# 1-Schematic_CarFan_controller_v2_1.net
KiCad netlist of a schematic drawn in EasyEDA
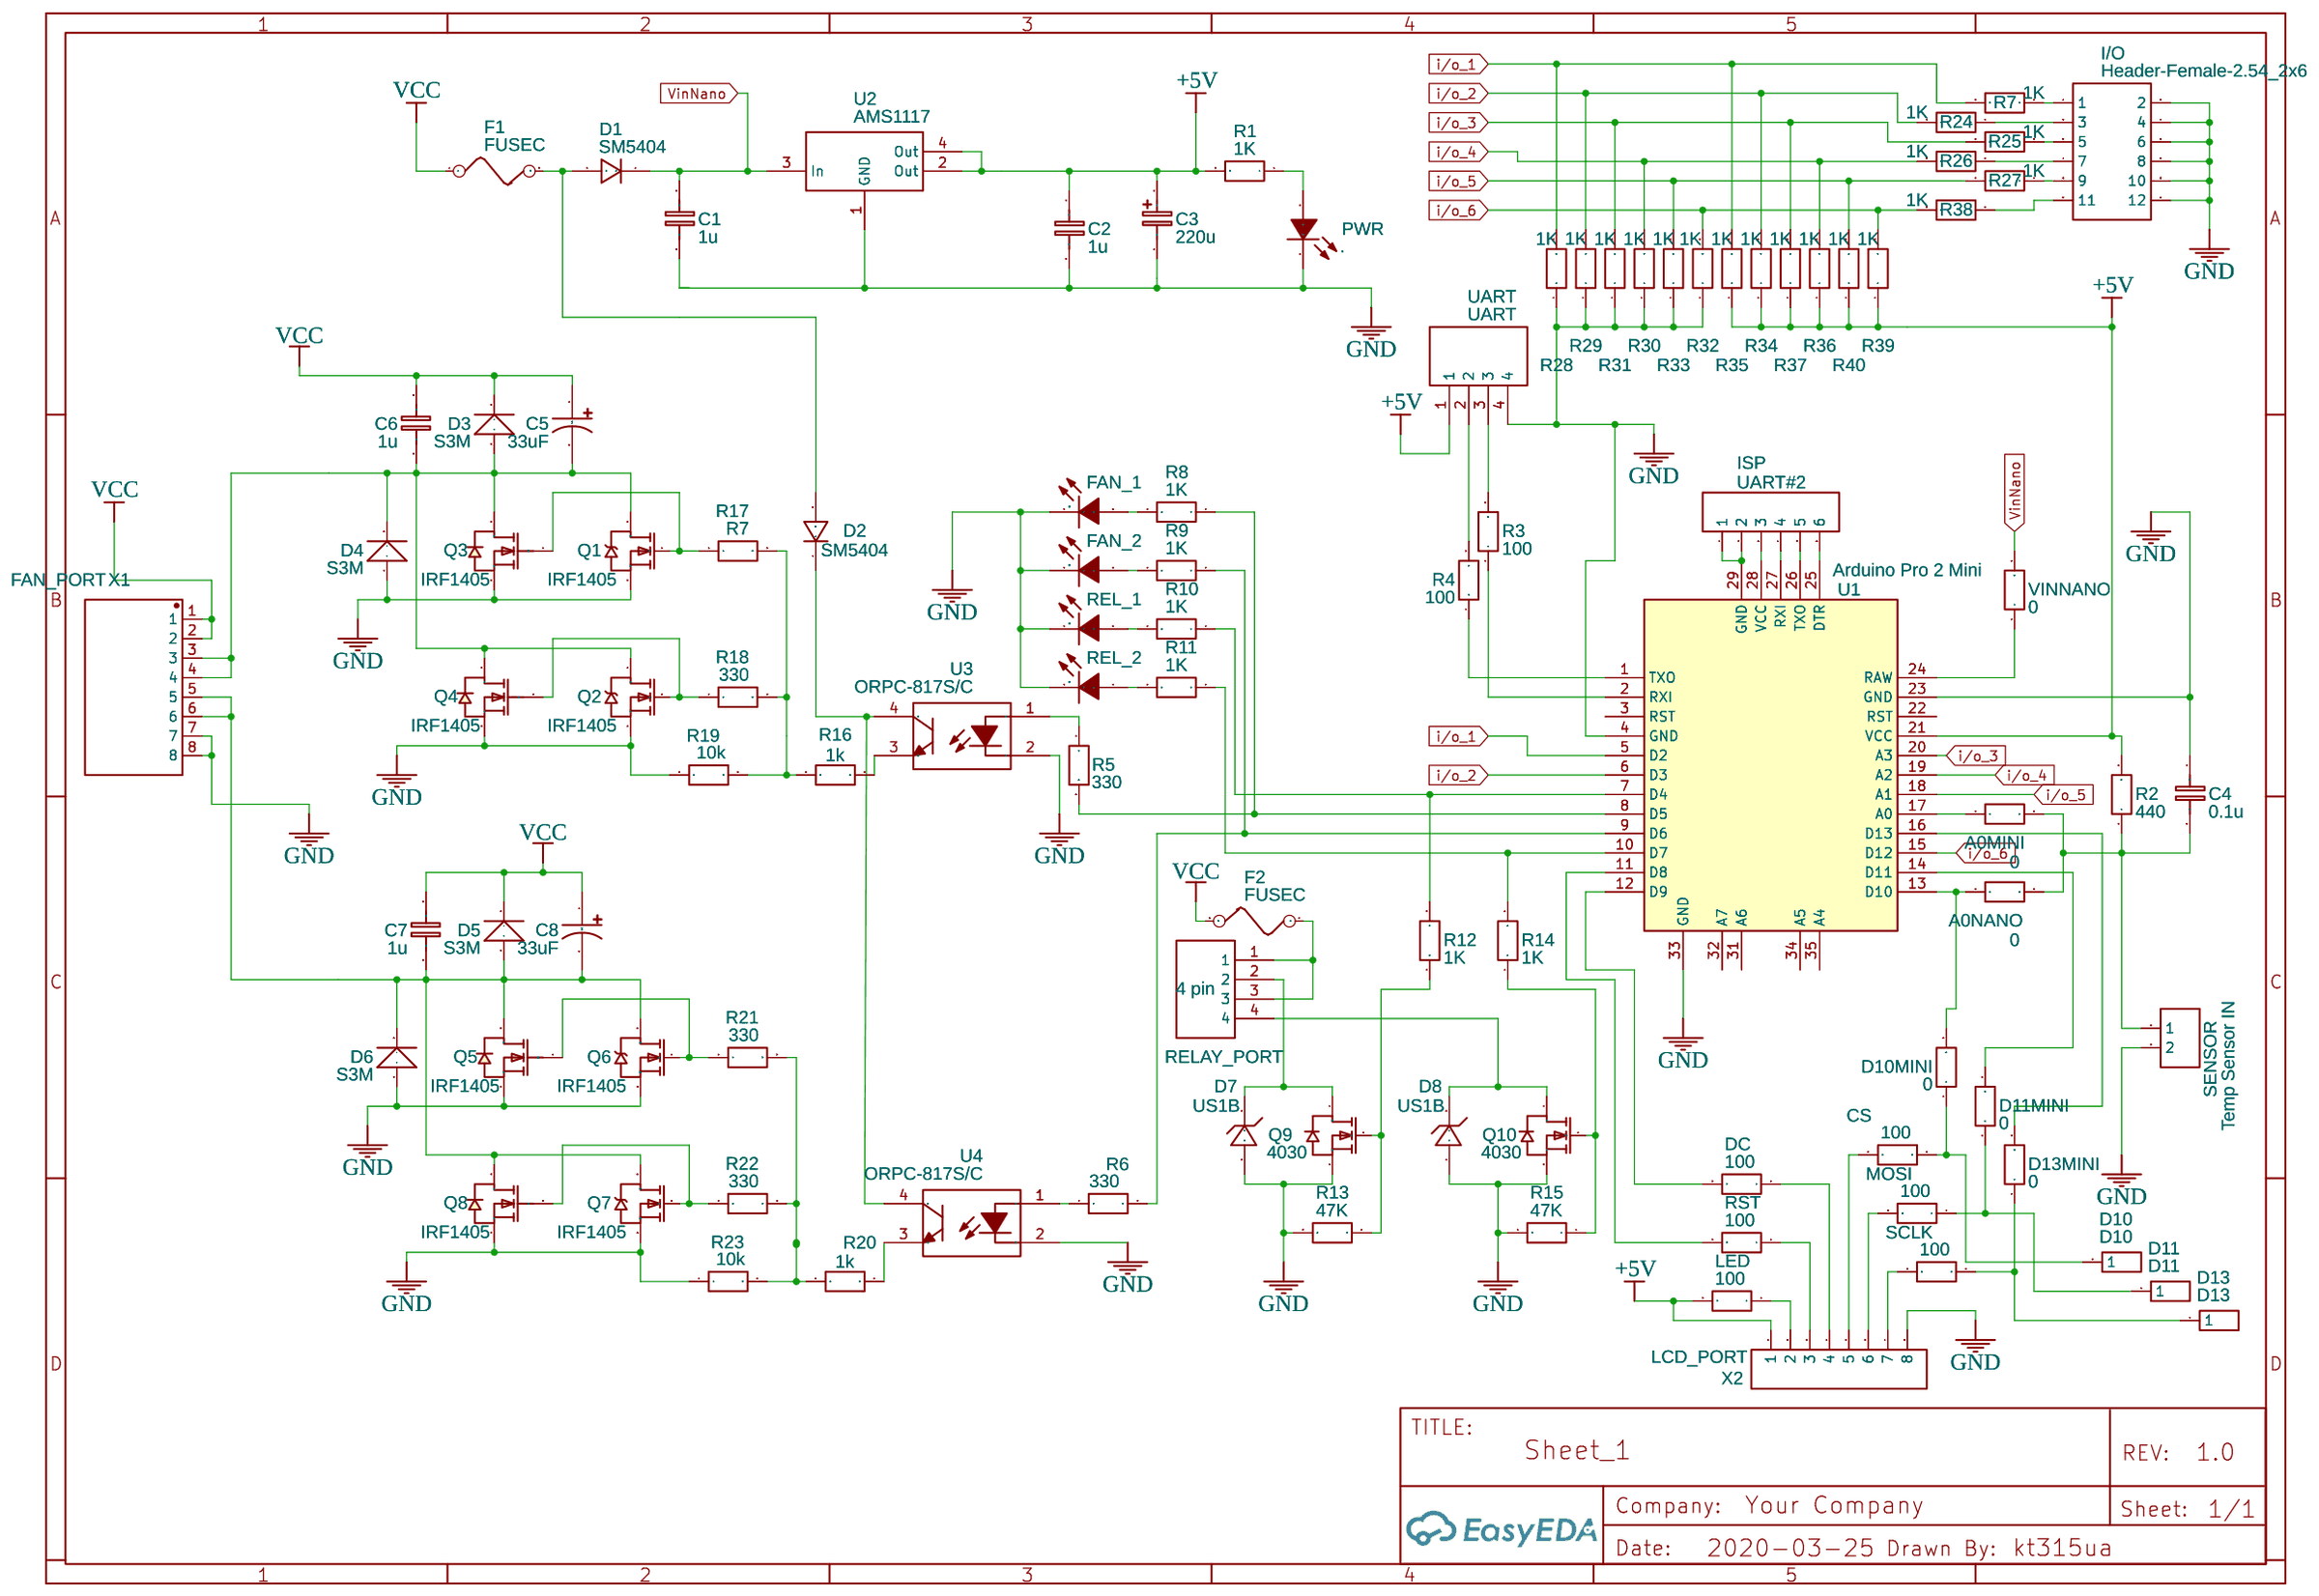
[diagram p0: schematic sheet]

(export (version "E")
  (design (tool "Eeschema 10.0.6"))
  (components
    (comp (ref "A0MINI") (value "0") (libsource (lib "") (part "Res_1206(1/4W)_EU_7")))
    (comp (ref "A0NANO") (value "0") (libsource (lib "") (part "Res_1206(1/4W)_EU_3")))
    (comp (ref "C1") (value "1u") (libsource (lib "") (part "Cap_1206_EU_4")))
    (comp (ref "C2") (value "1u") (libsource (lib "") (part "Cap_1206_EU_2")))
    (comp (ref "C3") (value "220u") (libsource (lib "") (part "Cap_Electrolytic(SMD)_D6.3XH5.5_EU")))
    (comp (ref "C4") (value "0.1u") (libsource (lib "") (part "Cap_1206_EU_3")))
    (comp (ref "C5")
      (value "33uF")
      (fields
        (field (name "BOM_Manufacturer Part") "EEEFK2A330P")
        (field (name "BOM_Supplier Part") "C178571")
      )
      (libsource (lib "") (part "EEEFK2A330P"))
    )
    (comp (ref "C6") (value "1u") (libsource (lib "") (part "Cap_1206_EU")))
    (comp (ref "C7") (value "1u") (libsource (lib "") (part "Cap_1206_EU_1")))
    (comp (ref "C8")
      (value "33uF")
      (fields
        (field (name "BOM_Manufacturer Part") "EEEFK2A330P")
        (field (name "BOM_Supplier Part") "C178571")
      )
      (libsource (lib "") (part "EEEFK2A330P"))
    )
    (comp (ref "CS") (value "100") (libsource (lib "") (part "Res_1206(1/4W)_EU_15")))
    (comp (ref "D1")
      (value "SM5404")
      (fields (field (name "BOM_Supplier Part") "C212808"))
      (libsource (lib "") (part "SM5404_1"))
    )
    (comp (ref "D2")
      (value "SM5404")
      (fields (field (name "BOM_Supplier Part") "C212808"))
      (libsource (lib "") (part "SM5404"))
    )
    (comp (ref "D3") (value "S3M") (libsource (lib "") (part "DDO-214AB")))
    (comp (ref "D4") (value "S3M") (libsource (lib "") (part "DDO-214AB")))
    (comp (ref "D5") (value "S3M") (libsource (lib "") (part "DDO-214AB")))
    (comp (ref "D6") (value "S3M") (libsource (lib "") (part "DDO-214AB")))
    (comp (ref "D7")
      (value "US1B")
      (fields
        (field (name "BOM_Manufacturer Part") "SMAZ12-13-F")
        (field (name "BOM_Supplier Part") "C110523")
      )
      (libsource (lib "") (part "SMAZ12-13-F(SMA(DO-214AC))"))
    )
    (comp (ref "D8")
      (value "US1B")
      (fields
        (field (name "BOM_Manufacturer Part") "SMAZ12-13-F")
        (field (name "BOM_Supplier Part") "C110523")
      )
      (libsource (lib "") (part "SMAZ12-13-F(SMA(DO-214AC))"))
    )
    (comp (ref "D10")
      (value "D10")
      (fields
        (field (name "BOM_Manufacturer Part") "Header-Male-2.54_1x1")
        (field (name "BOM_Supplier Part") "C81276")
      )
      (libsource (lib "") (part "Header-Male-2.54_1x1"))
    )
    (comp (ref "D10MINI") (value "0") (libsource (lib "") (part "Res_1206(1/4W)_EU_11")))
    (comp (ref "D11")
      (value "D11")
      (fields
        (field (name "BOM_Manufacturer Part") "Header-Male-2.54_1x1")
        (field (name "BOM_Supplier Part") "C81276")
      )
      (libsource (lib "") (part "Header-Male-2.54_1x1"))
    )
    (comp (ref "D11MINI") (value "0") (libsource (lib "") (part "Res_1206(1/4W)_EU_6")))
    (comp (ref "D13")
      (value "D13")
      (fields
        (field (name "BOM_Manufacturer Part") "Header-Male-2.54_1x1")
        (field (name "BOM_Supplier Part") "C81276")
      )
      (libsource (lib "") (part "Header-Male-2.54_1x1"))
    )
    (comp (ref "D13MINI") (value "0") (libsource (lib "") (part "Res_1206(1/4W)_EU_10")))
    (comp (ref "DC") (value "100") (libsource (lib "") (part "Res_1206(1/4W)_EU_14")))
    (comp (ref "F1") (value "FUSEC") (libsource (lib "") (part "FUSEC_1")))
    (comp (ref "F2") (value "FUSEC") (libsource (lib "") (part "FUSEC")))
    (comp (ref "FAN_1")
      (value ".")
      (fields
        (field (name "BOM_Manufacturer Part") "KT-1206Red LED")
        (field (name "BOM_Supplier Part") "C49018")
      )
      (libsource (lib "") (part "KT-1206Red LED"))
    )
    (comp (ref "FAN_2")
      (value ".")
      (fields
        (field (name "BOM_Manufacturer Part") "KT-1206Red LED")
        (field (name "BOM_Supplier Part") "C49018")
      )
      (libsource (lib "") (part "KT-1206Red LED"))
    )
    (comp (ref "FAN_PORT")
      (value "X1")
      (fields
        (field (name "BOM_Manufacturer Part") "Connector KF2510-8A")
        (field (name "BOM_Supplier Part") "C27837")
      )
      (libsource (lib "") (part "Connector_KF2510-8A-Fix"))
    )
    (comp (ref "I/O")
      (value "Header-Female-2.54_2x6")
      (fields (field (name "BOM_Supplier Part") "C36191"))
      (libsource (lib "") (part "Header-Female-2.54_2x6"))
    )
    (comp (ref "ISP")
      (value "UART#2")
      (fields
        (field (name "BOM_Manufacturer Part") "Female header 1*6p")
        (field (name "BOM_Supplier Part") "C40877")
      )
      (libsource (lib "") (part "Header-Female-2.54_1x6"))
    )
    (comp (ref "LCD_PORT")
      (value "X2")
      (fields
        (field (name "BOM_Manufacturer Part") "Female headerHDR1X8-2.54")
        (field (name "BOM_Supplier Part") "C27438")
      )
      (libsource (lib "") (part "Header-Female-2.54_1x8"))
    )
    (comp (ref "LED") (value "100") (libsource (lib "") (part "Res_1206(1/4W)_EU_13")))
    (comp (ref "MOSI") (value "100") (libsource (lib "") (part "Res_1206(1/4W)_EU_4")))
    (comp (ref "PWR")
      (value ".")
      (fields
        (field (name "BOM_Manufacturer Part") "KT-1206Red LED")
        (field (name "BOM_Supplier Part") "C49018")
      )
      (libsource (lib "") (part "KT-1206Red LED_2"))
    )
    (comp (ref "Q1")
      (value "IRF1405")
      (fields
        (field (name "BOM_Manufacturer Part") "IRF1405ZSTRLPBF")
        (field (name "BOM_Supplier Part") "C459941")
      )
      (libsource (lib "") (part "IRF1405ZSTRLPBF"))
    )
    (comp (ref "Q2")
      (value "IRF1405")
      (fields
        (field (name "BOM_Manufacturer Part") "IRF1405ZSTRLPBF")
        (field (name "BOM_Supplier Part") "C459941")
      )
      (libsource (lib "") (part "IRF1405ZSTRLPBF"))
    )
    (comp (ref "Q3")
      (value "IRF1405")
      (fields (field (name "BOM_Manufacturer Part") "IRF1405PBF") (field (name "BOM_Supplier Part") "C2559"))
      (libsource (lib "") (part "IRF1405PBF"))
    )
    (comp (ref "Q4")
      (value "IRF1405")
      (fields (field (name "BOM_Manufacturer Part") "IRF1405PBF") (field (name "BOM_Supplier Part") "C2559"))
      (libsource (lib "") (part "IRF1405PBF"))
    )
    (comp (ref "Q5")
      (value "IRF1405")
      (fields (field (name "BOM_Manufacturer Part") "IRF1405PBF") (field (name "BOM_Supplier Part") "C2559"))
      (libsource (lib "") (part "IRF1405PBF"))
    )
    (comp (ref "Q6")
      (value "IRF1405")
      (fields
        (field (name "BOM_Manufacturer Part") "IRF1405ZSTRLPBF")
        (field (name "BOM_Supplier Part") "C459941")
      )
      (libsource (lib "") (part "IRF1405ZSTRLPBF"))
    )
    (comp (ref "Q7")
      (value "IRF1405")
      (fields
        (field (name "BOM_Manufacturer Part") "IRF1405ZSTRLPBF")
        (field (name "BOM_Supplier Part") "C459941")
      )
      (libsource (lib "") (part "IRF1405ZSTRLPBF"))
    )
    (comp (ref "Q8")
      (value "IRF1405")
      (fields (field (name "BOM_Manufacturer Part") "IRF1405PBF") (field (name "BOM_Supplier Part") "C2559"))
      (libsource (lib "") (part "IRF1405PBF"))
    )
    (comp (ref "Q9")
      (value "4030")
      (fields
        (field (name "BOM_Manufacturer Part") "STD8N60DM2")
        (field (name "BOM_Supplier Part") "C457504")
      )
      (libsource (lib "") (part "STD8N60DM2"))
    )
    (comp (ref "Q10")
      (value "4030")
      (fields
        (field (name "BOM_Manufacturer Part") "STD8N60DM2")
        (field (name "BOM_Supplier Part") "C457504")
      )
      (libsource (lib "") (part "STD8N60DM2"))
    )
    (comp (ref "R1") (value "1K") (libsource (lib "") (part "Res_1206(1/4W)_EU_5")))
    (comp (ref "R2") (value "440") (libsource (lib "") (part "Res_1206(1/4W)_EU_1")))
    (comp (ref "R3") (value "100") (libsource (lib "") (part "Res_1206(1/4W)_EU_1")))
    (comp (ref "R4") (value "100") (libsource (lib "") (part "Res_1206(1/4W)_EU_1")))
    (comp (ref "R5") (value "330") (libsource (lib "") (part "Res_1206(1/4W)_EU_8")))
    (comp (ref "R6") (value "330") (libsource (lib "") (part "Res_1206(1/4W)_EU")))
    (comp (ref "R7") (value "1K") (libsource (lib "") (part "Res_1206(1/4W)_EU_5")))
    (comp (ref "R8") (value "1K") (libsource (lib "") (part "Res_1206(1/4W)_EU_5")))
    (comp (ref "R9") (value "1K") (libsource (lib "") (part "Res_1206(1/4W)_EU_5")))
    (comp (ref "R10") (value "1K") (libsource (lib "") (part "Res_1206(1/4W)_EU_5")))
    (comp (ref "R11") (value "1K") (libsource (lib "") (part "Res_1206(1/4W)_EU_5")))
    (comp (ref "R12") (value "1K") (libsource (lib "") (part "Res_1206(1/4W)_EU_1")))
    (comp (ref "R13") (value "47K") (libsource (lib "") (part "Res_1206(1/4W)_EU_5")))
    (comp (ref "R14") (value "1K") (libsource (lib "") (part "Res_1206(1/4W)_EU_1")))
    (comp (ref "R15") (value "47K") (libsource (lib "") (part "Res_1206(1/4W)_EU_5")))
    (comp (ref "R16") (value "1k") (libsource (lib "") (part "Res_1206(1/4W)_EU_5")))
    (comp (ref "R17") (value "R7") (libsource (lib "") (part "Res_1206(1/4W)_EU")))
    (comp (ref "R18") (value "330") (libsource (lib "") (part "Res_1206(1/4W)_EU")))
    (comp (ref "R19") (value "10k") (libsource (lib "") (part "Res_1206(1/4W)_EU")))
    (comp (ref "R20") (value "1k") (libsource (lib "") (part "Res_1206(1/4W)_EU_5")))
    (comp (ref "R21") (value "330") (libsource (lib "") (part "Res_1206(1/4W)_EU")))
    (comp (ref "R22") (value "330") (libsource (lib "") (part "Res_1206(1/4W)_EU")))
    (comp (ref "R23") (value "10k") (libsource (lib "") (part "Res_1206(1/4W)_EU")))
    (comp (ref "R24") (value "1K") (libsource (lib "") (part "Res_1206(1/4W)_EU_5")))
    (comp (ref "R25") (value "1K") (libsource (lib "") (part "Res_1206(1/4W)_EU_5")))
    (comp (ref "R26") (value "1K") (libsource (lib "") (part "Res_1206(1/4W)_EU_5")))
    (comp (ref "R27") (value "1K") (libsource (lib "") (part "Res_1206(1/4W)_EU_5")))
    (comp (ref "R28") (value "1K") (libsource (lib "") (part "Res_1206(1/4W)_EU_1")))
    (comp (ref "R29") (value "1K") (libsource (lib "") (part "Res_1206(1/4W)_EU_1")))
    (comp (ref "R30") (value "1K") (libsource (lib "") (part "Res_1206(1/4W)_EU_1")))
    (comp (ref "R31") (value "1K") (libsource (lib "") (part "Res_1206(1/4W)_EU_1")))
    (comp (ref "R32") (value "1K") (libsource (lib "") (part "Res_1206(1/4W)_EU_1")))
    (comp (ref "R33") (value "1K") (libsource (lib "") (part "Res_1206(1/4W)_EU_1")))
    (comp (ref "R34") (value "1K") (libsource (lib "") (part "Res_1206(1/4W)_EU_1")))
    (comp (ref "R35") (value "1K") (libsource (lib "") (part "Res_1206(1/4W)_EU_1")))
    (comp (ref "R36") (value "1K") (libsource (lib "") (part "Res_1206(1/4W)_EU_1")))
    (comp (ref "R37") (value "1K") (libsource (lib "") (part "Res_1206(1/4W)_EU_1")))
    (comp (ref "R38") (value "1K") (libsource (lib "") (part "Res_1206(1/4W)_EU_5")))
    (comp (ref "R39") (value "1K") (libsource (lib "") (part "Res_1206(1/4W)_EU_1")))
    (comp (ref "R40") (value "1K") (libsource (lib "") (part "Res_1206(1/4W)_EU_1")))
    (comp (ref "RELAY_PORT")
      (value "4 pin")
      (fields
        (field (name "BOM_Manufacturer Part") "220S-1*4P H=8.5MM Ytype Gold-plated")
        (field (name "BOM_Supplier Part") "C124413")
      )
      (libsource (lib "") (part "220S-1*4P H=8.5MM Ytype Gold-plated"))
    )
    (comp (ref "REL_1")
      (value ".")
      (fields
        (field (name "BOM_Manufacturer Part") "KT-1206Red LED")
        (field (name "BOM_Supplier Part") "C49018")
      )
      (libsource (lib "") (part "KT-1206Red LED_1"))
    )
    (comp (ref "REL_2")
      (value ".")
      (fields
        (field (name "BOM_Manufacturer Part") "KT-1206Red LED")
        (field (name "BOM_Supplier Part") "C49018")
      )
      (libsource (lib "") (part "KT-1206Red LED_1"))
    )
    (comp (ref "RST") (value "100") (libsource (lib "") (part "Res_1206(1/4W)_EU_2")))
    (comp (ref "SCLK") (value "100") (libsource (lib "") (part "Res_1206(1/4W)_EU_12")))
    (comp (ref "SENSOR")
      (value "Temp Sensor IN")
      (fields
        (field (name "BOM_Manufacturer Part") "2.54-1*2PFemale")
        (field (name "BOM_Supplier Part") "C49661")
      )
      (libsource (lib "") (part "Header-Female-2.54_1x2"))
    )
    (comp (ref "U1") (value "Arduino Pro 2 Mini") (libsource (lib "") (part "Arduino Pro 2 Mini_328_-_3.3V")))
    (comp (ref "U2")
      (value "AMS1117")
      (fields (field (name "BOM_Supplier Part") "C6186"))
      (libsource (lib "") (part "AMS1117"))
    )
    (comp (ref "U3")
      (value "ORPC-817S/C")
      (fields (field (name "BOM_Supplier Part") "C231230"))
      (libsource (lib "") (part "ORPC-817S/C"))
    )
    (comp (ref "U4")
      (value "ORPC-817S/C")
      (fields (field (name "BOM_Supplier Part") "C231230"))
      (libsource (lib "") (part "ORPC-817S/C"))
    )
    (comp (ref "UART")
      (value "UART")
      (fields
        (field (name "BOM_Manufacturer Part") "220S-1*4P H=8.5MM Ytype Gold-plated")
        (field (name "BOM_Supplier Part") "C124413")
      )
      (libsource (lib "") (part "220S-1*4P H=8.5MM Ytype Gold-plated_1"))
    )
    (comp (ref "VINNANO") (value "0") (libsource (lib "") (part "Res_1206(1/4W)_EU_9")))
  )
  (nets
    (net (code "1") (name "+5V") (class "Default")
      (node (ref "C2") (pin "1") (pinfunction "1_1") (pintype "unspecified"))
      (node (ref "C3") (pin "1") (pinfunction "1_1") (pintype "unspecified"))
      (node (ref "LCD_PORT") (pin "1") (pinfunction "1_1") (pintype "input"))
      (node (ref "LED") (pin "2") (pinfunction "2_2") (pintype "unspecified"))
      (node (ref "R1") (pin "2") (pinfunction "2_2") (pintype "unspecified"))
      (node (ref "R2") (pin "2") (pinfunction "2_2") (pintype "unspecified"))
      (node (ref "R34") (pin "1") (pinfunction "1_1") (pintype "unspecified"))
      (node (ref "R35") (pin "1") (pinfunction "1_1") (pintype "unspecified"))
      (node (ref "R36") (pin "1") (pinfunction "1_1") (pintype "unspecified"))
      (node (ref "R37") (pin "1") (pinfunction "1_1") (pintype "unspecified"))
      (node (ref "R39") (pin "1") (pinfunction "1_1") (pintype "unspecified"))
      (node (ref "R40") (pin "1") (pinfunction "1_1") (pintype "unspecified"))
      (node (ref "U1") (pin "21") (pinfunction "VCC_21") (pintype "unspecified"))
      (node (ref "U2") (pin "2") (pinfunction "Out_2") (pintype "unspecified"))
      (node (ref "U2") (pin "4") (pinfunction "Out_4") (pintype "unspecified"))
      (node (ref "UART") (pin "1") (pinfunction "1_1") (pintype "unspecified"))
    )
    (net (code "2") (name "GND") (class "Default")
      (node (ref "C1") (pin "2") (pinfunction "2_2") (pintype "unspecified"))
      (node (ref "C2") (pin "2") (pinfunction "2_2") (pintype "unspecified"))
      (node (ref "C3") (pin "2") (pinfunction "2_2") (pintype "unspecified"))
      (node (ref "C4") (pin "1") (pinfunction "1_1") (pintype "unspecified"))
      (node (ref "D4") (pin "1") (pinfunction "+_1") (pintype "unspecified"))
      (node (ref "D6") (pin "1") (pinfunction "+_1") (pintype "unspecified"))
      (node (ref "D7") (pin "1") (pinfunction "A_1") (pintype "unspecified"))
      (node (ref "D8") (pin "1") (pinfunction "A_1") (pintype "unspecified"))
      (node (ref "FAN_1") (pin "2") (pinfunction "K_2") (pintype "unspecified"))
      (node (ref "FAN_2") (pin "2") (pinfunction "K_2") (pintype "unspecified"))
      (node (ref "FAN_PORT") (pin "7") (pinfunction "7_7") (pintype "unspecified"))
      (node (ref "FAN_PORT") (pin "8") (pinfunction "8_8") (pintype "unspecified"))
      (node (ref "I/O") (pin "10") (pinfunction "10_10") (pintype "input"))
      (node (ref "I/O") (pin "12") (pinfunction "12_12") (pintype "input"))
      (node (ref "I/O") (pin "2") (pinfunction "2_2") (pintype "input"))
      (node (ref "I/O") (pin "4") (pinfunction "4_4") (pintype "input"))
      (node (ref "I/O") (pin "6") (pinfunction "6_6") (pintype "input"))
      (node (ref "I/O") (pin "8") (pinfunction "8_8") (pintype "input"))
      (node (ref "LCD_PORT") (pin "8") (pinfunction "8_8") (pintype "input"))
      (node (ref "PWR") (pin "2") (pinfunction "K_2") (pintype "unspecified"))
      (node (ref "Q1") (pin "3") (pinfunction "S_3") (pintype "unspecified"))
      (node (ref "Q10") (pin "3") (pinfunction "S_3") (pintype "unspecified"))
      (node (ref "Q2") (pin "3") (pinfunction "S_3") (pintype "unspecified"))
      (node (ref "Q3") (pin "3") (pinfunction "S_3") (pintype "unspecified"))
      (node (ref "Q4") (pin "3") (pinfunction "S_3") (pintype "unspecified"))
      (node (ref "Q5") (pin "3") (pinfunction "S_3") (pintype "unspecified"))
      (node (ref "Q6") (pin "3") (pinfunction "S_3") (pintype "unspecified"))
      (node (ref "Q7") (pin "3") (pinfunction "S_3") (pintype "unspecified"))
      (node (ref "Q8") (pin "3") (pinfunction "S_3") (pintype "unspecified"))
      (node (ref "Q9") (pin "3") (pinfunction "S_3") (pintype "unspecified"))
      (node (ref "R13") (pin "2") (pinfunction "2_2") (pintype "unspecified"))
      (node (ref "R15") (pin "2") (pinfunction "2_2") (pintype "unspecified"))
      (node (ref "R19") (pin "1") (pinfunction "1_1") (pintype "unspecified"))
      (node (ref "R23") (pin "1") (pinfunction "1_1") (pintype "unspecified"))
      (node (ref "R28") (pin "1") (pinfunction "1_1") (pintype "unspecified"))
      (node (ref "R29") (pin "1") (pinfunction "1_1") (pintype "unspecified"))
      (node (ref "R30") (pin "1") (pinfunction "1_1") (pintype "unspecified"))
      (node (ref "R31") (pin "1") (pinfunction "1_1") (pintype "unspecified"))
      (node (ref "R32") (pin "1") (pinfunction "1_1") (pintype "unspecified"))
      (node (ref "R33") (pin "1") (pinfunction "1_1") (pintype "unspecified"))
      (node (ref "REL_1") (pin "2") (pinfunction "K_2") (pintype "unspecified"))
      (node (ref "REL_2") (pin "2") (pinfunction "K_2") (pintype "unspecified"))
      (node (ref "SENSOR") (pin "2") (pinfunction "2_2") (pintype "input"))
      (node (ref "U1") (pin "23") (pinfunction "GND_23") (pintype "unspecified"))
      (node (ref "U1") (pin "33") (pinfunction "GND_33") (pintype "unspecified"))
      (node (ref "U1") (pin "4") (pinfunction "GND_4") (pintype "unspecified"))
      (node (ref "U2") (pin "1") (pinfunction "GND_1") (pintype "unspecified"))
      (node (ref "U3") (pin "2") (pinfunction "2_2") (pintype "unspecified"))
      (node (ref "U4") (pin "2") (pinfunction "2_2") (pintype "unspecified"))
      (node (ref "UART") (pin "4") (pinfunction "4_4") (pintype "unspecified"))
    )
    (net (code "3") (name "Net-(A0MINI-Pad2)") (class "Default")
      (node (ref "A0MINI") (pin "2") (pinfunction "2_2") (pintype "unspecified"))
      (node (ref "A0NANO") (pin "2") (pinfunction "2_2") (pintype "unspecified"))
      (node (ref "C4") (pin "2") (pinfunction "2_2") (pintype "unspecified"))
      (node (ref "R2") (pin "1") (pinfunction "1_1") (pintype "unspecified"))
      (node (ref "SENSOR") (pin "1") (pinfunction "1_1") (pintype "input"))
    )
    (net (code "4") (name "Net-(CS-Pad1)") (class "Default")
      (node (ref "CS") (pin "1") (pinfunction "1_1") (pintype "unspecified"))
      (node (ref "D10") (pin "1") (pinfunction "1_1") (pintype "input"))
      (node (ref "D10MINI") (pin "1") (pinfunction "1_1") (pintype "unspecified"))
    )
    (net (code "5") (name "Net-(CS-Pad2)") (class "Default")
      (node (ref "CS") (pin "2") (pinfunction "2_2") (pintype "unspecified"))
      (node (ref "LCD_PORT") (pin "5") (pinfunction "5_5") (pintype "input"))
    )
    (net (code "6") (name "Net-(D1-Pad2)") (class "Default")
      (node (ref "D1") (pin "2") (pinfunction "2_2") (pintype "unspecified"))
      (node (ref "D2") (pin "2") (pinfunction "2_2") (pintype "unspecified"))
      (node (ref "F1") (pin "2") (pinfunction "2_2") (pintype "unspecified"))
    )
    (net (code "7") (name "Net-(D2-Pad1)") (class "Default")
      (node (ref "D2") (pin "1") (pinfunction "1_1") (pintype "unspecified"))
      (node (ref "U3") (pin "4") (pinfunction "4_4") (pintype "unspecified"))
      (node (ref "U4") (pin "4") (pinfunction "4_4") (pintype "unspecified"))
    )
    (net (code "8") (name "Net-(D3-+)") (class "Default")
      (node (ref "C5") (pin "2") (pinfunction "2_2") (pintype "unspecified"))
      (node (ref "C6") (pin "2") (pinfunction "2_2") (pintype "unspecified"))
      (node (ref "D3") (pin "1") (pinfunction "+_1") (pintype "unspecified"))
      (node (ref "D4") (pin "2") (pinfunction "-_2") (pintype "unspecified"))
      (node (ref "FAN_PORT") (pin "3") (pinfunction "3_3") (pintype "unspecified"))
      (node (ref "FAN_PORT") (pin "4") (pinfunction "4_4") (pintype "unspecified"))
      (node (ref "Q1") (pin "2") (pinfunction "D_2") (pintype "unspecified"))
      (node (ref "Q2") (pin "2") (pinfunction "D_2") (pintype "unspecified"))
      (node (ref "Q3") (pin "2") (pinfunction "D_2") (pintype "unspecified"))
      (node (ref "Q4") (pin "2") (pinfunction "D_2") (pintype "unspecified"))
    )
    (net (code "9") (name "Net-(D5-+)") (class "Default")
      (node (ref "C7") (pin "2") (pinfunction "2_2") (pintype "unspecified"))
      (node (ref "C8") (pin "2") (pinfunction "2_2") (pintype "unspecified"))
      (node (ref "D5") (pin "1") (pinfunction "+_1") (pintype "unspecified"))
      (node (ref "D6") (pin "2") (pinfunction "-_2") (pintype "unspecified"))
      (node (ref "FAN_PORT") (pin "5") (pinfunction "5_5") (pintype "unspecified"))
      (node (ref "FAN_PORT") (pin "6") (pinfunction "6_6") (pintype "unspecified"))
      (node (ref "Q5") (pin "2") (pinfunction "D_2") (pintype "unspecified"))
      (node (ref "Q6") (pin "2") (pinfunction "D_2") (pintype "unspecified"))
      (node (ref "Q7") (pin "2") (pinfunction "D_2") (pintype "unspecified"))
      (node (ref "Q8") (pin "2") (pinfunction "D_2") (pintype "unspecified"))
    )
    (net (code "10") (name "Net-(D7-K)") (class "Default")
      (node (ref "D7") (pin "2") (pinfunction "K_2") (pintype "unspecified"))
      (node (ref "Q9") (pin "4") (pinfunction "D_4") (pintype "unspecified"))
      (node (ref "RELAY_PORT") (pin "2") (pinfunction "2_2") (pintype "unspecified"))
    )
    (net (code "11") (name "Net-(D8-K)") (class "Default")
      (node (ref "D8") (pin "2") (pinfunction "K_2") (pintype "unspecified"))
      (node (ref "Q10") (pin "4") (pinfunction "D_4") (pintype "unspecified"))
      (node (ref "RELAY_PORT") (pin "4") (pinfunction "4_4") (pintype "unspecified"))
    )
    (net (code "12") (name "Net-(D11-Pad1)") (class "Default")
      (node (ref "D11") (pin "1") (pinfunction "1_1") (pintype "input"))
      (node (ref "D11MINI") (pin "1") (pinfunction "1_1") (pintype "unspecified"))
      (node (ref "MOSI") (pin "1") (pinfunction "1_1") (pintype "unspecified"))
    )
    (net (code "13") (name "Net-(D13-Pad1)") (class "Default")
      (node (ref "D13") (pin "1") (pinfunction "1_1") (pintype "input"))
      (node (ref "D13MINI") (pin "1") (pinfunction "1_1") (pintype "unspecified"))
      (node (ref "SCLK") (pin "1") (pinfunction "1_1") (pintype "unspecified"))
    )
    (net (code "14") (name "Net-(DC-Pad1)") (class "Default")
      (node (ref "DC") (pin "1") (pinfunction "1_1") (pintype "unspecified"))
      (node (ref "LCD_PORT") (pin "4") (pinfunction "4_4") (pintype "input"))
    )
    (net (code "15") (name "Net-(F2-Pad1)") (class "Default")
      (node (ref "F2") (pin "1") (pinfunction "1_1") (pintype "unspecified"))
      (node (ref "RELAY_PORT") (pin "1") (pinfunction "1_1") (pintype "unspecified"))
      (node (ref "RELAY_PORT") (pin "3") (pinfunction "3_3") (pintype "unspecified"))
    )
    (net (code "16") (name "Net-(FAN_1-A)") (class "Default")
      (node (ref "FAN_1") (pin "1") (pinfunction "A_1") (pintype "unspecified"))
      (node (ref "R8") (pin "2") (pinfunction "2_2") (pintype "unspecified"))
    )
    (net (code "17") (name "Net-(FAN_2-A)") (class "Default")
      (node (ref "FAN_2") (pin "1") (pinfunction "A_1") (pintype "unspecified"))
      (node (ref "R9") (pin "2") (pinfunction "2_2") (pintype "unspecified"))
    )
    (net (code "18") (name "Net-(I/O-Pad1)") (class "Default")
      (node (ref "I/O") (pin "1") (pinfunction "1_1") (pintype "input"))
      (node (ref "R7") (pin "1") (pinfunction "1_1") (pintype "unspecified"))
    )
    (net (code "19") (name "Net-(I/O-Pad3)") (class "Default")
      (node (ref "I/O") (pin "3") (pinfunction "3_3") (pintype "input"))
      (node (ref "R24") (pin "1") (pinfunction "1_1") (pintype "unspecified"))
    )
    (net (code "20") (name "Net-(I/O-Pad5)") (class "Default")
      (node (ref "I/O") (pin "5") (pinfunction "5_5") (pintype "input"))
      (node (ref "R25") (pin "1") (pinfunction "1_1") (pintype "unspecified"))
    )
    (net (code "21") (name "Net-(I/O-Pad7)") (class "Default")
      (node (ref "I/O") (pin "7") (pinfunction "7_7") (pintype "input"))
      (node (ref "R26") (pin "1") (pinfunction "1_1") (pintype "unspecified"))
    )
    (net (code "22") (name "Net-(I/O-Pad9)") (class "Default")
      (node (ref "I/O") (pin "9") (pinfunction "9_9") (pintype "input"))
      (node (ref "R27") (pin "1") (pinfunction "1_1") (pintype "unspecified"))
    )
    (net (code "23") (name "Net-(I/O-Pad11)") (class "Default")
      (node (ref "I/O") (pin "11") (pinfunction "11_11") (pintype "input"))
      (node (ref "R38") (pin "1") (pinfunction "1_1") (pintype "unspecified"))
    )
    (net (code "24") (name "Net-(ISP-Pad1)") (class "Default")
      (node (ref "ISP") (pin "1") (pinfunction "1_1") (pintype "input"))
      (node (ref "ISP") (pin "2") (pinfunction "2_2") (pintype "input"))
      (node (ref "U1") (pin "29") (pinfunction "GND_29") (pintype "unspecified"))
    )
    (net (code "25") (name "Net-(ISP-Pad3)") (class "Default")
      (node (ref "ISP") (pin "3") (pinfunction "3_3") (pintype "input"))
      (node (ref "U1") (pin "28") (pinfunction "VCC_28") (pintype "unspecified"))
    )
    (net (code "26") (name "Net-(ISP-Pad4)") (class "Default")
      (node (ref "ISP") (pin "4") (pinfunction "4_4") (pintype "input"))
      (node (ref "U1") (pin "27") (pinfunction "RXI_27") (pintype "unspecified"))
    )
    (net (code "27") (name "Net-(ISP-Pad5)") (class "Default")
      (node (ref "ISP") (pin "5") (pinfunction "5_5") (pintype "input"))
      (node (ref "U1") (pin "26") (pinfunction "TXO_26") (pintype "unspecified"))
    )
    (net (code "28") (name "Net-(LCD_PORT-Pad2)") (class "Default")
      (node (ref "LCD_PORT") (pin "2") (pinfunction "2_2") (pintype "input"))
      (node (ref "LED") (pin "1") (pinfunction "1_1") (pintype "unspecified"))
    )
    (net (code "29") (name "Net-(LCD_PORT-Pad3)") (class "Default")
      (node (ref "LCD_PORT") (pin "3") (pinfunction "3_3") (pintype "input"))
      (node (ref "RST") (pin "1") (pinfunction "1_1") (pintype "unspecified"))
    )
    (net (code "30") (name "Net-(LCD_PORT-Pad6)") (class "Default")
      (node (ref "LCD_PORT") (pin "6") (pinfunction "6_6") (pintype "input"))
      (node (ref "MOSI") (pin "2") (pinfunction "2_2") (pintype "unspecified"))
    )
    (net (code "31") (name "Net-(LCD_PORT-Pad7)") (class "Default")
      (node (ref "LCD_PORT") (pin "7") (pinfunction "7_7") (pintype "input"))
      (node (ref "SCLK") (pin "2") (pinfunction "2_2") (pintype "unspecified"))
    )
    (net (code "32") (name "Net-(PWR-A)") (class "Default")
      (node (ref "PWR") (pin "1") (pinfunction "A_1") (pintype "unspecified"))
      (node (ref "R1") (pin "1") (pinfunction "1_1") (pintype "unspecified"))
    )
    (net (code "33") (name "Net-(Q1-G)") (class "Default")
      (node (ref "Q1") (pin "1") (pinfunction "G_1") (pintype "unspecified"))
      (node (ref "Q3") (pin "1") (pinfunction "G_1") (pintype "unspecified"))
      (node (ref "R17") (pin "1") (pinfunction "1_1") (pintype "unspecified"))
    )
    (net (code "34") (name "Net-(Q2-G)") (class "Default")
      (node (ref "Q2") (pin "1") (pinfunction "G_1") (pintype "unspecified"))
      (node (ref "Q4") (pin "1") (pinfunction "G_1") (pintype "unspecified"))
      (node (ref "R18") (pin "1") (pinfunction "1_1") (pintype "unspecified"))
    )
    (net (code "35") (name "Net-(Q5-G)") (class "Default")
      (node (ref "Q5") (pin "1") (pinfunction "G_1") (pintype "unspecified"))
      (node (ref "Q6") (pin "1") (pinfunction "G_1") (pintype "unspecified"))
      (node (ref "R21") (pin "1") (pinfunction "1_1") (pintype "unspecified"))
    )
    (net (code "36") (name "Net-(Q7-G)") (class "Default")
      (node (ref "Q7") (pin "1") (pinfunction "G_1") (pintype "unspecified"))
      (node (ref "Q8") (pin "1") (pinfunction "G_1") (pintype "unspecified"))
      (node (ref "R22") (pin "1") (pinfunction "1_1") (pintype "unspecified"))
    )
    (net (code "37") (name "Net-(Q9-G)") (class "Default")
      (node (ref "Q9") (pin "1") (pinfunction "G_1") (pintype "unspecified"))
      (node (ref "R12") (pin "1") (pinfunction "1_1") (pintype "unspecified"))
      (node (ref "R13") (pin "1") (pinfunction "1_1") (pintype "unspecified"))
    )
    (net (code "38") (name "Net-(Q10-G)") (class "Default")
      (node (ref "Q10") (pin "1") (pinfunction "G_1") (pintype "unspecified"))
      (node (ref "R14") (pin "1") (pinfunction "1_1") (pintype "unspecified"))
      (node (ref "R15") (pin "1") (pinfunction "1_1") (pintype "unspecified"))
    )
    (net (code "39") (name "Net-(R3-Pad1)") (class "Default")
      (node (ref "R3") (pin "1") (pinfunction "1_1") (pintype "unspecified"))
      (node (ref "U1") (pin "2") (pinfunction "RXI_2") (pintype "unspecified"))
    )
    (net (code "40") (name "Net-(R3-Pad2)") (class "Default")
      (node (ref "R3") (pin "2") (pinfunction "2_2") (pintype "unspecified"))
      (node (ref "UART") (pin "3") (pinfunction "3_3") (pintype "unspecified"))
    )
    (net (code "41") (name "Net-(R4-Pad1)") (class "Default")
      (node (ref "R4") (pin "1") (pinfunction "1_1") (pintype "unspecified"))
      (node (ref "U1") (pin "1") (pinfunction "TXO_1") (pintype "unspecified"))
    )
    (net (code "42") (name "Net-(R4-Pad2)") (class "Default")
      (node (ref "R4") (pin "2") (pinfunction "2_2") (pintype "unspecified"))
      (node (ref "UART") (pin "2") (pinfunction "2_2") (pintype "unspecified"))
    )
    (net (code "43") (name "Net-(R5-Pad1)") (class "Default")
      (node (ref "R5") (pin "1") (pinfunction "1_1") (pintype "unspecified"))
      (node (ref "U3") (pin "1") (pinfunction "1_1") (pintype "unspecified"))
    )
    (net (code "44") (name "Net-(R6-Pad1)") (class "Default")
      (node (ref "R6") (pin "1") (pinfunction "1_1") (pintype "unspecified"))
      (node (ref "U4") (pin "1") (pinfunction "1_1") (pintype "unspecified"))
    )
    (net (code "45") (name "Net-(R16-Pad1)") (class "Default")
      (node (ref "R16") (pin "1") (pinfunction "1_1") (pintype "unspecified"))
      (node (ref "U3") (pin "3") (pinfunction "3_3") (pintype "unspecified"))
    )
    (net (code "46") (name "Net-(R16-Pad2)") (class "Default")
      (node (ref "R16") (pin "2") (pinfunction "2_2") (pintype "unspecified"))
      (node (ref "R17") (pin "2") (pinfunction "2_2") (pintype "unspecified"))
      (node (ref "R18") (pin "2") (pinfunction "2_2") (pintype "unspecified"))
      (node (ref "R19") (pin "2") (pinfunction "2_2") (pintype "unspecified"))
    )
    (net (code "47") (name "Net-(R20-Pad1)") (class "Default")
      (node (ref "R20") (pin "1") (pinfunction "1_1") (pintype "unspecified"))
      (node (ref "U4") (pin "3") (pinfunction "3_3") (pintype "unspecified"))
    )
    (net (code "48") (name "Net-(R20-Pad2)") (class "Default")
      (node (ref "R20") (pin "2") (pinfunction "2_2") (pintype "unspecified"))
      (node (ref "R21") (pin "2") (pinfunction "2_2") (pintype "unspecified"))
      (node (ref "R22") (pin "2") (pinfunction "2_2") (pintype "unspecified"))
      (node (ref "R23") (pin "2") (pinfunction "2_2") (pintype "unspecified"))
    )
    (net (code "49") (name "Net-(REL_1-A)") (class "Default")
      (node (ref "R10") (pin "2") (pinfunction "2_2") (pintype "unspecified"))
      (node (ref "REL_1") (pin "1") (pinfunction "A_1") (pintype "unspecified"))
    )
    (net (code "50") (name "Net-(REL_2-A)") (class "Default")
      (node (ref "R11") (pin "2") (pinfunction "2_2") (pintype "unspecified"))
      (node (ref "REL_2") (pin "1") (pinfunction "A_1") (pintype "unspecified"))
    )
    (net (code "51") (name "Net-(U1-A0)") (class "Default")
      (node (ref "A0MINI") (pin "1") (pinfunction "1_1") (pintype "unspecified"))
      (node (ref "U1") (pin "17") (pinfunction "A0_17") (pintype "unspecified"))
    )
    (net (code "52") (name "Net-(U1-D4)") (class "Default")
      (node (ref "R10") (pin "1") (pinfunction "1_1") (pintype "unspecified"))
      (node (ref "R12") (pin "2") (pinfunction "2_2") (pintype "unspecified"))
      (node (ref "U1") (pin "7") (pinfunction "D4_7") (pintype "unspecified"))
    )
    (net (code "53") (name "Net-(U1-D5)") (class "Default")
      (node (ref "R5") (pin "2") (pinfunction "2_2") (pintype "unspecified"))
      (node (ref "R8") (pin "1") (pinfunction "1_1") (pintype "unspecified"))
      (node (ref "U1") (pin "8") (pinfunction "D5_8") (pintype "unspecified"))
    )
    (net (code "54") (name "Net-(U1-D6)") (class "Default")
      (node (ref "R6") (pin "2") (pinfunction "2_2") (pintype "unspecified"))
      (node (ref "R9") (pin "1") (pinfunction "1_1") (pintype "unspecified"))
      (node (ref "U1") (pin "9") (pinfunction "D6_9") (pintype "unspecified"))
    )
    (net (code "55") (name "Net-(U1-D7)") (class "Default")
      (node (ref "R11") (pin "1") (pinfunction "1_1") (pintype "unspecified"))
      (node (ref "R14") (pin "2") (pinfunction "2_2") (pintype "unspecified"))
      (node (ref "U1") (pin "10") (pinfunction "D7_10") (pintype "unspecified"))
    )
    (net (code "56") (name "Net-(U1-D8)") (class "Default")
      (node (ref "RST") (pin "2") (pinfunction "2_2") (pintype "unspecified"))
      (node (ref "U1") (pin "11") (pinfunction "D8_11") (pintype "unspecified"))
    )
    (net (code "57") (name "Net-(U1-D9)") (class "Default")
      (node (ref "DC") (pin "2") (pinfunction "2_2") (pintype "unspecified"))
      (node (ref "U1") (pin "12") (pinfunction "D9_12") (pintype "unspecified"))
    )
    (net (code "58") (name "Net-(U1-D10)") (class "Default")
      (node (ref "A0NANO") (pin "1") (pinfunction "1_1") (pintype "unspecified"))
      (node (ref "D10MINI") (pin "2") (pinfunction "2_2") (pintype "unspecified"))
      (node (ref "U1") (pin "13") (pinfunction "D10_13") (pintype "unspecified"))
    )
    (net (code "59") (name "Net-(U1-D11)") (class "Default")
      (node (ref "D11MINI") (pin "2") (pinfunction "2_2") (pintype "unspecified"))
      (node (ref "U1") (pin "14") (pinfunction "D11_14") (pintype "unspecified"))
    )
    (net (code "60") (name "Net-(U1-D13)") (class "Default")
      (node (ref "D13MINI") (pin "2") (pinfunction "2_2") (pintype "unspecified"))
      (node (ref "U1") (pin "16") (pinfunction "D13_16") (pintype "unspecified"))
    )
    (net (code "61") (name "Net-(U1-DTR)") (class "Default")
      (node (ref "ISP") (pin "6") (pinfunction "6_6") (pintype "input"))
      (node (ref "U1") (pin "25") (pinfunction "DTR_25") (pintype "unspecified"))
    )
    (net (code "62") (name "Net-(U1-RAW)") (class "Default")
      (node (ref "U1") (pin "24") (pinfunction "RAW_24") (pintype "unspecified"))
      (node (ref "VINNANO") (pin "1") (pinfunction "1_1") (pintype "unspecified"))
    )
    (net (code "63") (name "VCC") (class "Default")
      (node (ref "C5") (pin "1") (pinfunction "1_1") (pintype "unspecified"))
      (node (ref "C6") (pin "1") (pinfunction "1_1") (pintype "unspecified"))
      (node (ref "C7") (pin "1") (pinfunction "1_1") (pintype "unspecified"))
      (node (ref "C8") (pin "1") (pinfunction "1_1") (pintype "unspecified"))
      (node (ref "D3") (pin "2") (pinfunction "-_2") (pintype "unspecified"))
      (node (ref "D5") (pin "2") (pinfunction "-_2") (pintype "unspecified"))
      (node (ref "F1") (pin "1") (pinfunction "1_1") (pintype "unspecified"))
      (node (ref "F2") (pin "2") (pinfunction "2_2") (pintype "unspecified"))
      (node (ref "FAN_PORT") (pin "1") (pinfunction "1_1") (pintype "unspecified"))
      (node (ref "FAN_PORT") (pin "2") (pinfunction "2_2") (pintype "unspecified"))
    )
    (net (code "64") (name "VinNano") (class "Default")
      (node (ref "C1") (pin "1") (pinfunction "1_1") (pintype "unspecified"))
      (node (ref "D1") (pin "1") (pinfunction "1_1") (pintype "unspecified"))
      (node (ref "U2") (pin "3") (pinfunction "In_3") (pintype "unspecified"))
      (node (ref "VINNANO") (pin "2") (pinfunction "2_2") (pintype "unspecified"))
    )
    (net (code "65") (name "i{slash}o_1") (class "Default")
      (node (ref "R28") (pin "2") (pinfunction "2_2") (pintype "unspecified"))
      (node (ref "R35") (pin "2") (pinfunction "2_2") (pintype "unspecified"))
      (node (ref "R7") (pin "2") (pinfunction "2_2") (pintype "unspecified"))
      (node (ref "U1") (pin "5") (pinfunction "D2_5") (pintype "unspecified"))
    )
    (net (code "66") (name "i{slash}o_2") (class "Default")
      (node (ref "R24") (pin "2") (pinfunction "2_2") (pintype "unspecified"))
      (node (ref "R29") (pin "2") (pinfunction "2_2") (pintype "unspecified"))
      (node (ref "R34") (pin "2") (pinfunction "2_2") (pintype "unspecified"))
      (node (ref "U1") (pin "6") (pinfunction "D3_6") (pintype "unspecified"))
    )
    (net (code "67") (name "i{slash}o_3") (class "Default")
      (node (ref "R25") (pin "2") (pinfunction "2_2") (pintype "unspecified"))
      (node (ref "R31") (pin "2") (pinfunction "2_2") (pintype "unspecified"))
      (node (ref "R37") (pin "2") (pinfunction "2_2") (pintype "unspecified"))
      (node (ref "U1") (pin "20") (pinfunction "A3_20") (pintype "unspecified"))
    )
    (net (code "68") (name "i{slash}o_4") (class "Default")
      (node (ref "R26") (pin "2") (pinfunction "2_2") (pintype "unspecified"))
      (node (ref "R30") (pin "2") (pinfunction "2_2") (pintype "unspecified"))
      (node (ref "R36") (pin "2") (pinfunction "2_2") (pintype "unspecified"))
      (node (ref "U1") (pin "19") (pinfunction "A2_19") (pintype "unspecified"))
    )
    (net (code "69") (name "i{slash}o_5") (class "Default")
      (node (ref "R27") (pin "2") (pinfunction "2_2") (pintype "unspecified"))
      (node (ref "R33") (pin "2") (pinfunction "2_2") (pintype "unspecified"))
      (node (ref "R40") (pin "2") (pinfunction "2_2") (pintype "unspecified"))
      (node (ref "U1") (pin "18") (pinfunction "A1_18") (pintype "unspecified"))
    )
    (net (code "70") (name "i{slash}o_6") (class "Default")
      (node (ref "R32") (pin "2") (pinfunction "2_2") (pintype "unspecified"))
      (node (ref "R38") (pin "2") (pinfunction "2_2") (pintype "unspecified"))
      (node (ref "R39") (pin "2") (pinfunction "2_2") (pintype "unspecified"))
      (node (ref "U1") (pin "15") (pinfunction "D12_15") (pintype "unspecified"))
    )
    (net (code "71") (name "unconnected-(U1-A4-Pad35)") (class "Default")
      (node (ref "U1") (pin "35") (pinfunction "A4_35") (pintype "unspecified"))
    )
    (net (code "72") (name "unconnected-(U1-A5-Pad34)") (class "Default")
      (node (ref "U1") (pin "34") (pinfunction "A5_34") (pintype "unspecified"))
    )
    (net (code "73") (name "unconnected-(U1-A6-Pad31)") (class "Default")
      (node (ref "U1") (pin "31") (pinfunction "A6_31") (pintype "unspecified"))
    )
    (net (code "74") (name "unconnected-(U1-A7-Pad32)") (class "Default")
      (node (ref "U1") (pin "32") (pinfunction "A7_32") (pintype "unspecified"))
    )
    (net (code "75") (name "unconnected-(U1-RST-Pad3)") (class "Default")
      (node (ref "U1") (pin "3") (pinfunction "RST_3") (pintype "unspecified"))
    )
    (net (code "76") (name "unconnected-(U1-RST-Pad22)") (class "Default")
      (node (ref "U1") (pin "22") (pinfunction "RST_22") (pintype "unspecified"))
    )
  )
)
